# DIV2_8B.net
KiCad netlist of a schematic drawn in Altium Designer
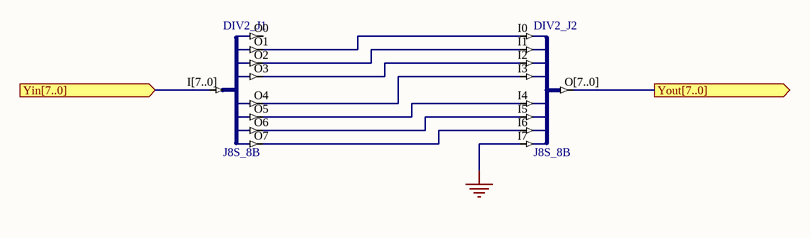
[diagram p0: DIV2_8B.SCHDOC]

(export (version "E")
  (design (tool "Eeschema 10.0.6"))
  (components
    (comp (ref "DIV2_J1")
      (value "J8S_8B")
      (description "8-Bit input bus to 8 single pin outputs")
      (fields (field (name "PUBLISHER") "Altium Limited"))
      (libsource (lib "FPGA Generic") (part "J8B_8S"))
    )
    (comp (ref "DIV2_J2")
      (value "J8S_8B")
      (description "8 Single pin inputs to single 8-Bit output bus")
      (fields (field (name "PUBLISHER") "Altium Limited"))
      (libsource (lib "FPGA Generic") (part "J8S_8B"))
    )
  )
  (nets
    (net (code "17") (name "/Yin[7..0]") (class "Default")
      (node (ref "DIV2_J1") (pin "I[7..0]") (pinfunction "I[7..0]_I[7..0]") (pintype "input"))
    )
    (net (code "18") (name "/Yout[7..0]") (class "Default")
      (node (ref "DIV2_J2") (pin "O[7..0]") (pinfunction "O[7..0]_O[7..0]") (pintype "output"))
    )
    (net (code "19") (name "GND") (class "Default")
      (node (ref "DIV2_J2") (pin "I7") (pinfunction "I7_I7") (pintype "input"))
    )
    (net (code "20") (name "Net-(DIV2_J1-PadO1)") (class "Default")
      (node (ref "DIV2_J1") (pin "O1") (pinfunction "O1_O1") (pintype "output"))
      (node (ref "DIV2_J2") (pin "I0") (pinfunction "I0_I0") (pintype "input"))
    )
    (net (code "21") (name "Net-(DIV2_J1-PadO2)") (class "Default")
      (node (ref "DIV2_J1") (pin "O2") (pinfunction "O2_O2") (pintype "output"))
      (node (ref "DIV2_J2") (pin "I1") (pinfunction "I1_I1") (pintype "input"))
    )
    (net (code "22") (name "Net-(DIV2_J1-PadO3)") (class "Default")
      (node (ref "DIV2_J1") (pin "O3") (pinfunction "O3_O3") (pintype "output"))
      (node (ref "DIV2_J2") (pin "I2") (pinfunction "I2_I2") (pintype "input"))
    )
    (net (code "23") (name "Net-(DIV2_J1-PadO4)") (class "Default")
      (node (ref "DIV2_J1") (pin "O4") (pinfunction "O4_O4") (pintype "output"))
      (node (ref "DIV2_J2") (pin "I3") (pinfunction "I3_I3") (pintype "input"))
    )
    (net (code "24") (name "Net-(DIV2_J1-PadO5)") (class "Default")
      (node (ref "DIV2_J1") (pin "O5") (pinfunction "O5_O5") (pintype "output"))
      (node (ref "DIV2_J2") (pin "I4") (pinfunction "I4_I4") (pintype "input"))
    )
    (net (code "25") (name "Net-(DIV2_J1-PadO6)") (class "Default")
      (node (ref "DIV2_J1") (pin "O6") (pinfunction "O6_O6") (pintype "output"))
      (node (ref "DIV2_J2") (pin "I5") (pinfunction "I5_I5") (pintype "input"))
    )
    (net (code "26") (name "Net-(DIV2_J1-PadO7)") (class "Default")
      (node (ref "DIV2_J1") (pin "O7") (pinfunction "O7_O7") (pintype "output"))
      (node (ref "DIV2_J2") (pin "I6") (pinfunction "I6_I6") (pintype "input"))
    )
    (net (code "27") (name "unconnected-(DIV2_J1-PadO0)") (class "Default")
      (node (ref "DIV2_J1") (pin "O0") (pinfunction "O0_O0") (pintype "output"))
    )
  )
)
